# 05_Pressure_and_LoadCell.net
KiCad netlist of a schematic drawn in Altium Designer
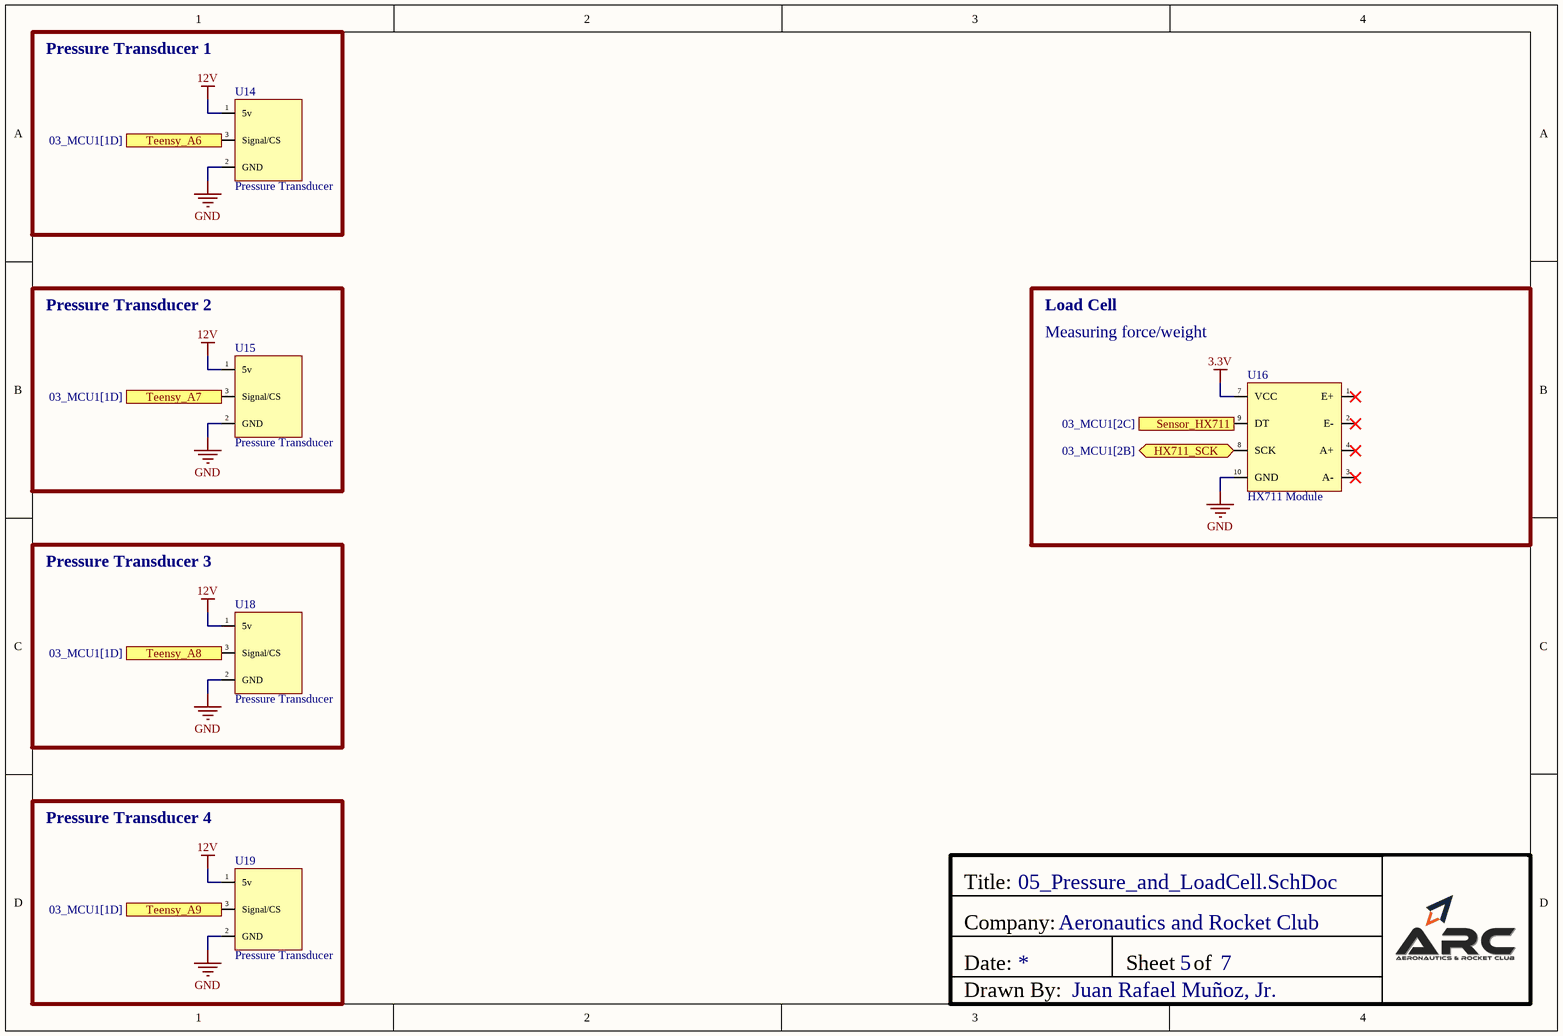
[diagram p0: 05_Pressure_and_LoadCell.SchDoc]

(export (version "E")
  (design (tool "Eeschema 10.0.6"))
  (components
    (comp (ref "U14")
      (value "Pressure Transducer")
      (footprint "3-PIN AVIATION CONNECTOR")
      (libsource (lib "Ground Support_Schlib") (part "Pressure Transducer"))
    )
    (comp (ref "U15")
      (value "Pressure Transducer")
      (footprint "3-PIN AVIATION CONNECTOR")
      (libsource (lib "Ground Support_Schlib") (part "Pressure Transducer"))
    )
    (comp (ref "U16")
      (value "HX711 Module")
      (footprint "HX711 Module")
      (libsource (lib "Ground Support_Schlib") (part "HX711 Module"))
    )
    (comp (ref "U18")
      (value "Pressure Transducer")
      (footprint "3-PIN AVIATION CONNECTOR")
      (libsource (lib "Ground Support_Schlib") (part "Pressure Transducer"))
    )
    (comp (ref "U19")
      (value "Pressure Transducer")
      (footprint "3-PIN AVIATION CONNECTOR")
      (libsource (lib "Ground Support_Schlib") (part "Pressure Transducer"))
    )
  )
  (nets
    (net (code "1") (name "/HX711_SCK") (class "Default")
      (node (ref "U16") (pin "8") (pinfunction "SCK_8") (pintype "passive"))
    )
    (net (code "2") (name "/Sensor_HX711") (class "Default")
      (node (ref "U16") (pin "9") (pinfunction "DT_9") (pintype "passive"))
    )
    (net (code "3") (name "/Teensy_A6") (class "Default")
      (node (ref "U14") (pin "3") (pinfunction "Signal/CS_3") (pintype "passive"))
    )
    (net (code "4") (name "/Teensy_A7") (class "Default")
      (node (ref "U15") (pin "3") (pinfunction "Signal/CS_3") (pintype "passive"))
    )
    (net (code "5") (name "/Teensy_A8") (class "Default")
      (node (ref "U18") (pin "3") (pinfunction "Signal/CS_3") (pintype "passive"))
    )
    (net (code "6") (name "/Teensy_A9") (class "Default")
      (node (ref "U19") (pin "3") (pinfunction "Signal/CS_3") (pintype "passive"))
    )
    (net (code "7") (name "3.3V") (class "Default")
      (node (ref "U16") (pin "7") (pinfunction "VCC_7") (pintype "power_in"))
    )
    (net (code "8") (name "12V") (class "Default")
      (node (ref "U14") (pin "1") (pinfunction "5v_1") (pintype "power_in"))
      (node (ref "U15") (pin "1") (pinfunction "5v_1") (pintype "power_in"))
      (node (ref "U18") (pin "1") (pinfunction "5v_1") (pintype "power_in"))
      (node (ref "U19") (pin "1") (pinfunction "5v_1") (pintype "power_in"))
    )
    (net (code "9") (name "GND") (class "Default")
      (node (ref "U14") (pin "2") (pinfunction "GND_2") (pintype "power_in"))
      (node (ref "U15") (pin "2") (pinfunction "GND_2") (pintype "power_in"))
      (node (ref "U16") (pin "10") (pinfunction "GND_10") (pintype "power_in"))
      (node (ref "U18") (pin "2") (pinfunction "GND_2") (pintype "power_in"))
      (node (ref "U19") (pin "2") (pinfunction "GND_2") (pintype "power_in"))
    )
    (net (code "10") (name "unconnected-(U16-A+-Pad4)") (class "Default")
      (node (ref "U16") (pin "4") (pinfunction "A+_4") (pintype "passive+no_connect"))
    )
    (net (code "11") (name "unconnected-(U16-A--Pad3)") (class "Default")
      (node (ref "U16") (pin "3") (pinfunction "A-_3") (pintype "passive+no_connect"))
    )
    (net (code "12") (name "unconnected-(U16-E+-Pad1)") (class "Default")
      (node (ref "U16") (pin "1") (pinfunction "E+_1") (pintype "passive+no_connect"))
    )
    (net (code "13") (name "unconnected-(U16-E--Pad2)") (class "Default")
      (node (ref "U16") (pin "2") (pinfunction "E-_2") (pintype "passive+no_connect"))
    )
  )
)
